# v1_0.net
KiCad netlist of a schematic drawn in Altium Designer
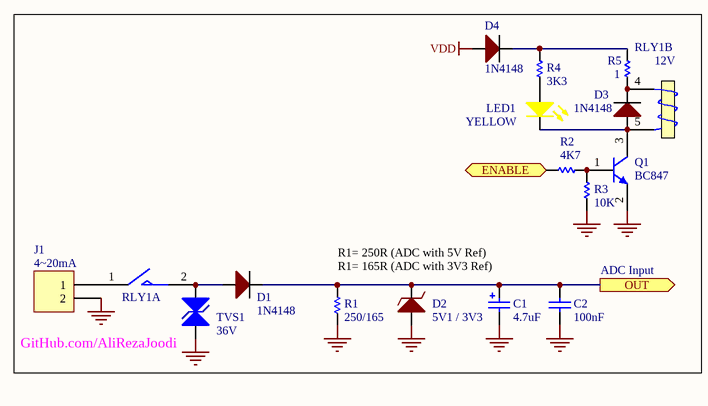
[diagram p0: v1.0.SchDoc]

(export (version "E")
  (design (tool "Eeschema 10.0.6"))
  (components
    (comp (ref "C1")
      (value "4.7uF")
      (footprint "CAPPR2.5-6.3x5")
      (description "Polarized Capacitor (Radial)")
      (fields (field (name "MANUFACTURER") "Generic Components") (field (name "PUBLISHER") "Altium Limited"))
      (libsource (lib "Miscellaneous Devices") (part "Cap Pol1"))
    )
    (comp (ref "C2")
      (value "100nF")
      (footprint "CAPNTO2.54-3.05x1.78A")
      (description "Capacitor")
      (fields (field (name "MANUFACTURER") "Generic Components") (field (name "PUBLISHER") "Altium Limited"))
      (libsource (lib "Miscellaneous Devices") (part "Cap"))
    )
    (comp (ref "D1")
      (value "1N4148")
      (footprint "D_THD_AXIAL0.3_DO-35")
      (description "Diode,")
      (libsource (lib "Passive") (part "Diode_2Form"))
    )
    (comp (ref "D2")
      (value "5V1 / 3V3")
      (footprint "D_THD_AXIAL0.3_DO-35")
      (description "Diode, Zener")
      (libsource (lib "Passive") (part "Diode_Zener"))
    )
    (comp (ref "D3")
      (value "1N4148")
      (footprint "D_THD_AXIAL0.3_DO-35")
      (description "Diode,")
      (libsource (lib "Passive") (part "Diode_2Form"))
    )
    (comp (ref "D4")
      (value "1N4148")
      (footprint "D_THD_AXIAL0.3_DO-35")
      (description "Diode,")
      (libsource (lib "Passive") (part "Diode_2Form"))
    )
    (comp (ref "J1")
      (value "Header 2")
      (footprint "Fonics_2PIN_1")
      (description "Header, 2-Pin")
      (fields (field (name "PUBLISHER") "Altium Limited"))
      (libsource (lib "Miscellaneous Connectors") (part "Header 2"))
    )
    (comp (ref "LED1")
      (value "YELLOW")
      (footprint "LED_THD_3MM_YELLOW_R")
      (description "LED, Yellow")
      (fields (field (name "MANUFACTURER") "Generic Components") (field (name "PUBLISHER") "Altium Limited"))
      (libsource (lib "Display") (part "LED_YELLOW"))
    )
    (comp (ref "Q1")
      (value "Q1")
      (footprint "SOT23-3N")
      (description "Silicon Bipolar Transistor")
      (fields (field (name "ALTIUM_VALUE") "BC847"))
      (libsource (lib "my Libraries") (part "BC847"))
    )
    (comp (ref "R1")
      (value "250/165")
      (footprint "R_THD_AXIAL0.4(1/4W)")
      (description "Resistor")
      (libsource (lib "Passive") (part "Resistor"))
    )
    (comp (ref "R2")
      (value "4K7")
      (footprint "R_THD_AXIAL0.4(1/4W)")
      (description "Resistor")
      (libsource (lib "Passive") (part "Resistor"))
    )
    (comp (ref "R3")
      (value "10K")
      (footprint "R_THD_AXIAL0.4(1/4W)")
      (description "Resistor")
      (libsource (lib "Passive") (part "Resistor"))
    )
    (comp (ref "R4")
      (value "3K3")
      (footprint "R_THD_AXIAL0.4(1/4W)")
      (description "Resistor")
      (libsource (lib "Passive") (part "Resistor"))
    )
    (comp (ref "R5")
      (value "1")
      (footprint "R_THD_AXIAL0.4(1/4W)")
      (description "Resistor")
      (libsource (lib "Passive") (part "Resistor"))
    )
    (comp (ref "RLY1")
      (value "RELAU")
      (footprint "RELAY-SPDT-2")
      (fields (field (name "PUBLISHER") "Altium Limited"))
      (libsource (lib "my Libraries") (part "RELAY-NY12W-K"))
    )
    (comp (ref "TVS1")
      (value "36V")
      (footprint "D_THD_AXIAL0.6_DO-27_DO-201A_2Form")
      (description "Diode, TVS")
      (libsource (lib "Passive") (part "Diode_TVS"))
    )
  )
  (nets
    (net (code "1") (name "/ENABLE") (class "Default")
      (node (ref "R2") (pin "2") (pinfunction "2_2") (pintype "passive"))
    )
    (net (code "2") (name "/OUT") (class "Default")
      (node (ref "C1") (pin "1") (pinfunction "1_1") (pintype "passive"))
      (node (ref "C2") (pin "2") (pinfunction "2_2") (pintype "passive"))
      (node (ref "D1") (pin "2") (pinfunction "K_2") (pintype "passive"))
      (node (ref "D2") (pin "2") (pinfunction "2_2") (pintype "passive"))
      (node (ref "R1") (pin "1") (pinfunction "1_1") (pintype "passive"))
    )
    (net (code "3") (name "GND") (class "Default")
      (node (ref "C1") (pin "2") (pinfunction "2_2") (pintype "passive"))
      (node (ref "C2") (pin "1") (pinfunction "1_1") (pintype "passive"))
      (node (ref "D2") (pin "1") (pinfunction "1_1") (pintype "passive"))
      (node (ref "J1") (pin "2") (pinfunction "2_2") (pintype "passive"))
      (node (ref "Q1") (pin "2") (pinfunction "E_2") (pintype "passive"))
      (node (ref "R1") (pin "2") (pinfunction "2_2") (pintype "passive"))
      (node (ref "R3") (pin "1") (pinfunction "1_1") (pintype "passive"))
      (node (ref "TVS1") (pin "1") (pinfunction "1_1") (pintype "passive"))
    )
    (net (code "4") (name "Net-(D1-A)") (class "Default")
      (node (ref "D1") (pin "1") (pinfunction "A_1") (pintype "passive"))
      (node (ref "RLY1") (pin "2") (pinfunction "NO_2") (pintype "passive"))
      (node (ref "TVS1") (pin "2") (pinfunction "2_2") (pintype "passive"))
    )
    (net (code "5") (name "Net-(D3-A)") (class "Default")
      (node (ref "D3") (pin "1") (pinfunction "A_1") (pintype "passive"))
      (node (ref "LED1") (pin "2") (pinfunction "K_2") (pintype "passive"))
      (node (ref "Q1") (pin "3") (pinfunction "C_3") (pintype "passive"))
      (node (ref "RLY1") (pin "5") (pinfunction "T2_5") (pintype "passive"))
    )
    (net (code "6") (name "Net-(D3-K)") (class "Default")
      (node (ref "D3") (pin "2") (pinfunction "K_2") (pintype "passive"))
      (node (ref "R5") (pin "2") (pinfunction "2_2") (pintype "passive"))
      (node (ref "RLY1") (pin "4") (pinfunction "T1_4") (pintype "passive"))
    )
    (net (code "7") (name "Net-(D4-K)") (class "Default")
      (node (ref "D4") (pin "2") (pinfunction "K_2") (pintype "passive"))
      (node (ref "R4") (pin "2") (pinfunction "2_2") (pintype "passive"))
      (node (ref "R5") (pin "1") (pinfunction "1_1") (pintype "passive"))
    )
    (net (code "8") (name "Net-(LED1-A)") (class "Default")
      (node (ref "LED1") (pin "1") (pinfunction "A_1") (pintype "passive"))
      (node (ref "R4") (pin "1") (pinfunction "1_1") (pintype "passive"))
    )
    (net (code "9") (name "Net-(Q1-B)") (class "Default")
      (node (ref "Q1") (pin "1") (pinfunction "B_1") (pintype "passive"))
      (node (ref "R2") (pin "1") (pinfunction "1_1") (pintype "passive"))
      (node (ref "R3") (pin "2") (pinfunction "2_2") (pintype "passive"))
    )
    (net (code "10") (name "Net-(RLY1A-COM)") (class "Default")
      (node (ref "J1") (pin "1") (pinfunction "1_1") (pintype "passive"))
      (node (ref "RLY1") (pin "1") (pinfunction "COM_1") (pintype "passive"))
    )
    (net (code "11") (name "VDD") (class "Default")
      (node (ref "D4") (pin "1") (pinfunction "A_1") (pintype "passive"))
    )
  )
)
